# 15_BoardPowerSupply.net
KiCad netlist of a schematic drawn in Altium Designer
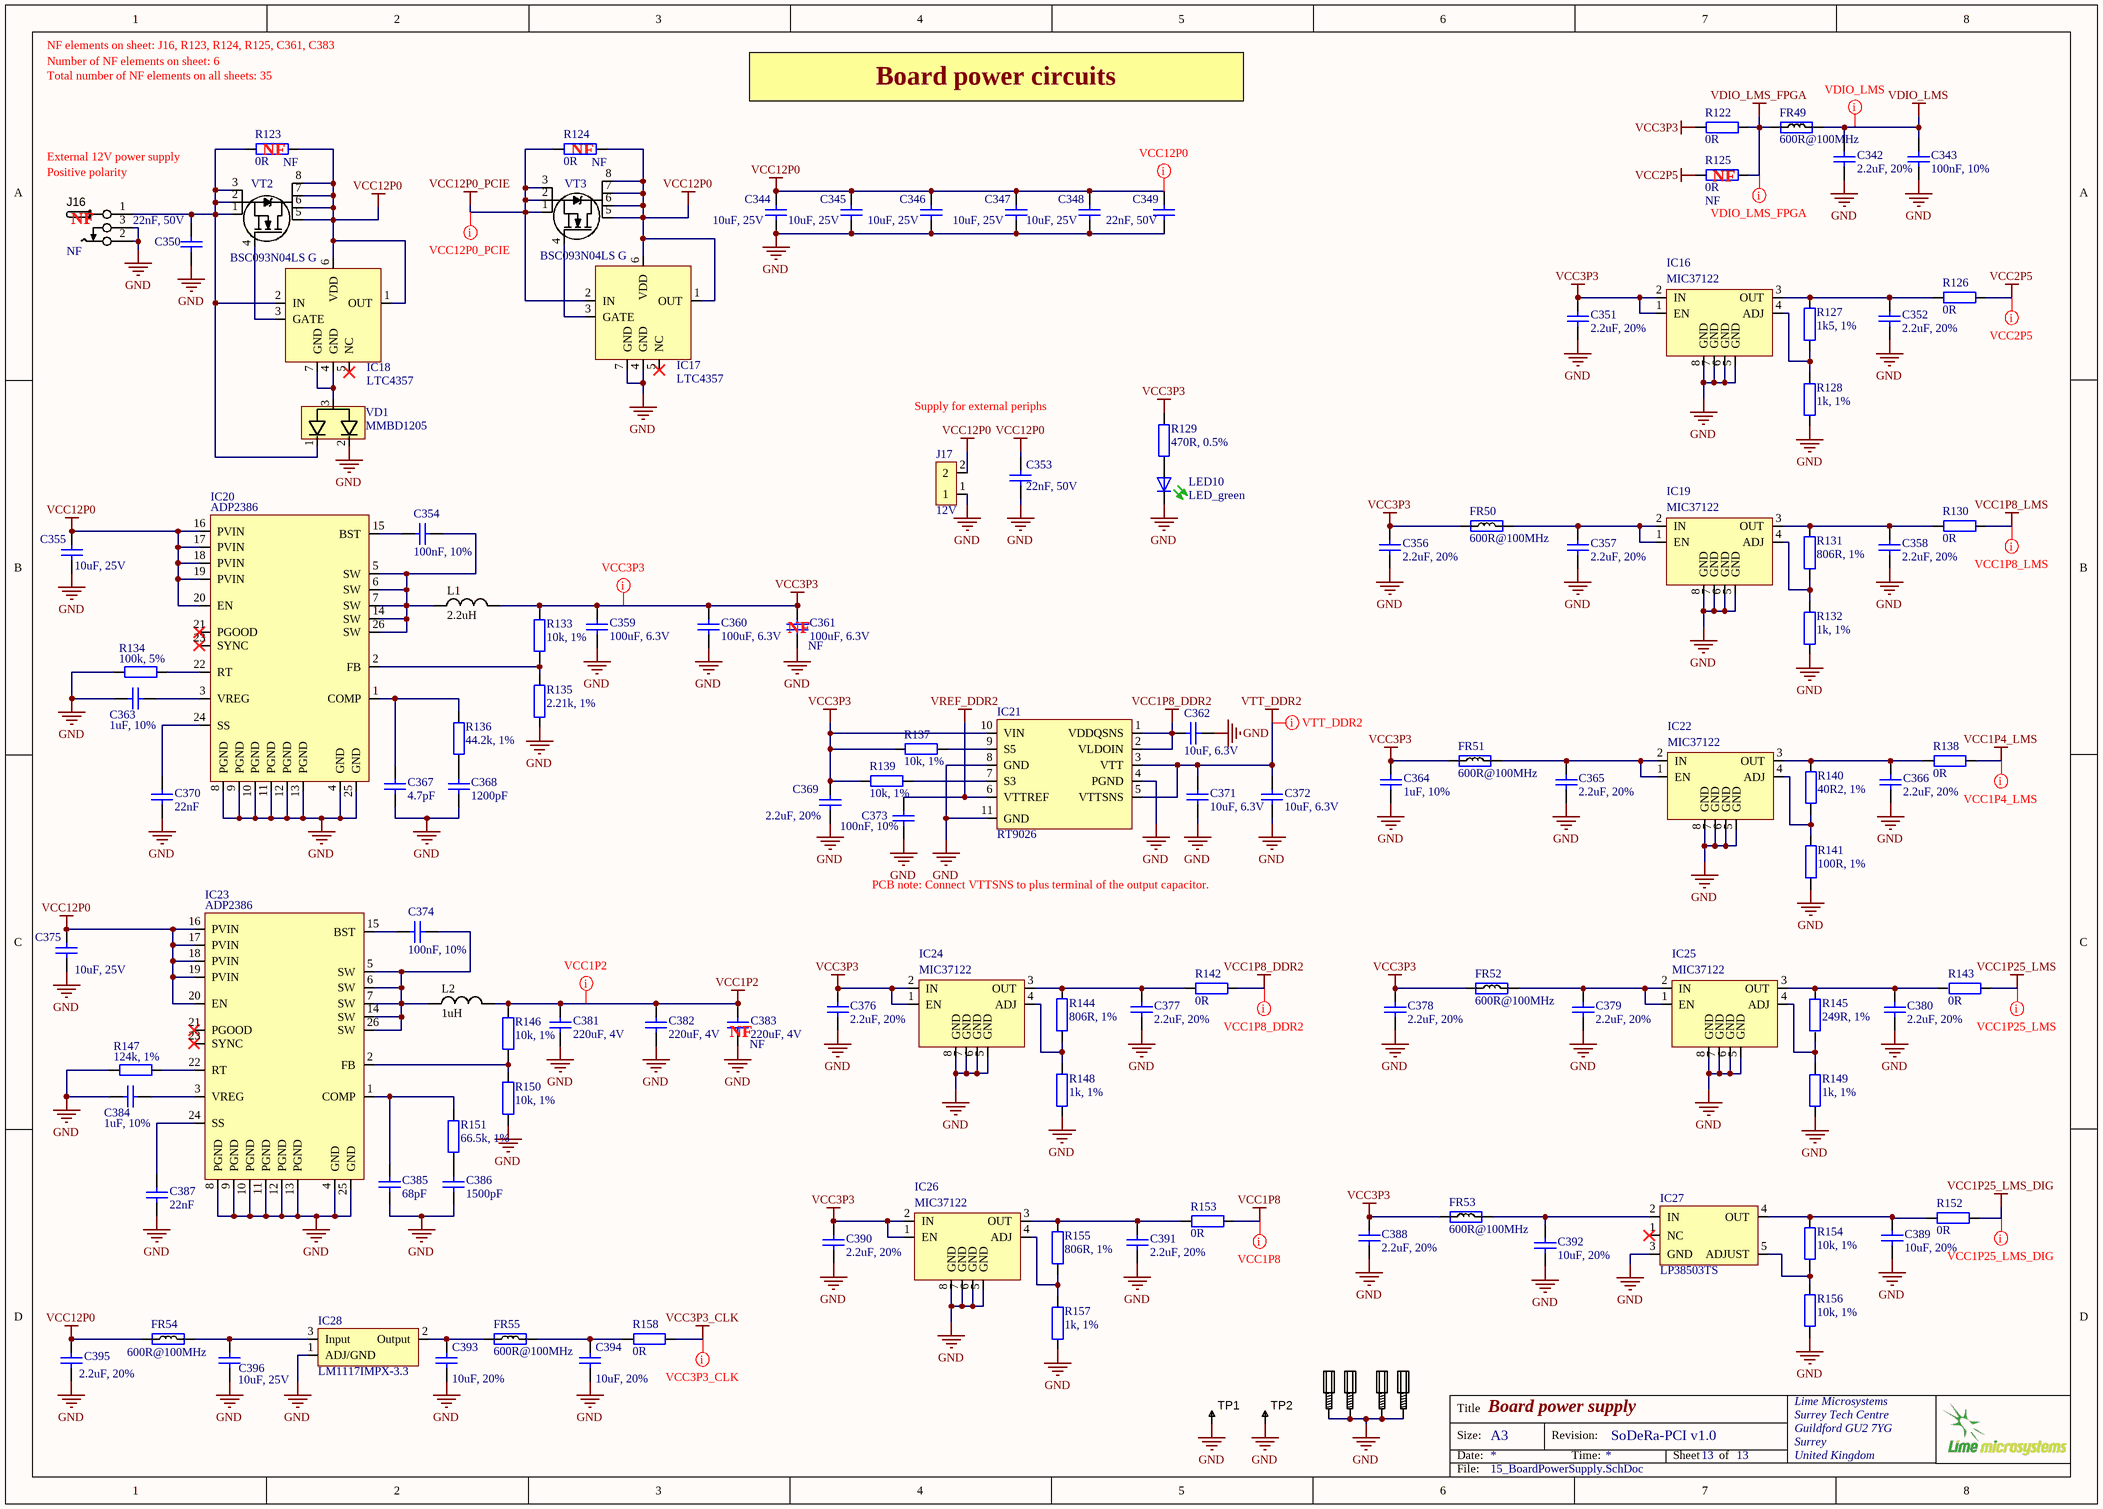
[diagram p0: 15_BoardPowerSupply.SchDoc]

(export (version "E")
  (design (tool "Eeschema 10.0.6"))
  (components
    (comp (ref "C342")
      (value "2.2uF, 20%")
      (footprint "LimeMicroAltiumLib_pcbLib:CAP0402")
      (fields (field (name "MANUFACTURER") "TDK Corporation") (field (name "TOLERANCE") "±20%"))
      (libsource (lib "LimeMicroAltiumLib_schLib") (part "Cap_0402"))
    )
    (comp (ref "C343")
      (value "100nF, 10%")
      (footprint "LimeMicroAltiumLib_pcbLib:CAP0402")
      (fields
        (field (name "MANUFACTURER") "Murata Electronics")
        (field (name "TOLERANCE") "10 %")
        (field (name "MANUFACTURER PART NUMBER") "GRM155R71C104KA88D")
      )
      (libsource (lib "LimeMicroAltiumLib_schLib") (part "Cap_0402"))
    )
    (comp (ref "C344")
      (value "10uF, 25V")
      (footprint "LimeMicroAltiumLib_pcbLib:CAP0603")
      (fields
        (field (name "MANUFACTURER") "Murata Electronics North America")
        (field (name "MANUFACTURER PART NUMBER") "GRM188R61E106MA73D")
        (field (name "TOLERANCE") "±20%")
      )
      (libsource (lib "LimeMicroAltiumLib_schLib") (part "Cap_0603"))
    )
    (comp (ref "C345")
      (value "10uF, 25V")
      (footprint "LimeMicroAltiumLib_pcbLib:CAP0603")
      (fields
        (field (name "MANUFACTURER") "Murata Electronics North America")
        (field (name "MANUFACTURER PART NUMBER") "GRM188R61E106MA73D")
        (field (name "TOLERANCE") "±20%")
      )
      (libsource (lib "LimeMicroAltiumLib_schLib") (part "Cap_0603"))
    )
    (comp (ref "C346")
      (value "10uF, 25V")
      (footprint "LimeMicroAltiumLib_pcbLib:CAP0603")
      (fields
        (field (name "MANUFACTURER") "Murata Electronics North America")
        (field (name "MANUFACTURER PART NUMBER") "GRM188R61E106MA73D")
        (field (name "TOLERANCE") "±20%")
      )
      (libsource (lib "LimeMicroAltiumLib_schLib") (part "Cap_0603"))
    )
    (comp (ref "C347")
      (value "10uF, 25V")
      (footprint "LimeMicroAltiumLib_pcbLib:CAP0603")
      (fields
        (field (name "MANUFACTURER") "Murata Electronics North America")
        (field (name "MANUFACTURER PART NUMBER") "GRM188R61E106MA73D")
        (field (name "TOLERANCE") "±20%")
      )
      (libsource (lib "LimeMicroAltiumLib_schLib") (part "Cap_0603"))
    )
    (comp (ref "C348")
      (value "10uF, 25V")
      (footprint "LimeMicroAltiumLib_pcbLib:CAP0603")
      (fields
        (field (name "MANUFACTURER") "Murata Electronics North America")
        (field (name "MANUFACTURER PART NUMBER") "GRM188R61E106MA73D")
        (field (name "TOLERANCE") "±20%")
      )
      (libsource (lib "LimeMicroAltiumLib_schLib") (part "Cap_0603"))
    )
    (comp (ref "C349")
      (value "22nF, 50V")
      (footprint "LimeMicroAltiumLib_pcbLib:CAP0402")
      (fields (field (name "TOLERANCE") "±10%") (field (name "MANUFACTURER") "Kemet"))
      (libsource (lib "LimeMicroAltiumLib_schLib") (part "Cap_0402"))
    )
    (comp (ref "C350")
      (value "22nF, 50V")
      (footprint "LimeMicroAltiumLib_pcbLib:CAP0402")
      (fields (field (name "TOLERANCE") "±10%") (field (name "MANUFACTURER") "Kemet"))
      (libsource (lib "LimeMicroAltiumLib_schLib") (part "Cap_0402"))
    )
    (comp (ref "C351")
      (value "2.2uF, 20%")
      (footprint "LimeMicroAltiumLib_pcbLib:CAP0402")
      (fields (field (name "MANUFACTURER") "TDK Corporation") (field (name "TOLERANCE") "±20%"))
      (libsource (lib "LimeMicroAltiumLib_schLib") (part "Cap_0402"))
    )
    (comp (ref "C352")
      (value "2.2uF, 20%")
      (footprint "LimeMicroAltiumLib_pcbLib:CAP0402")
      (fields (field (name "MANUFACTURER") "TDK Corporation") (field (name "TOLERANCE") "±20%"))
      (libsource (lib "LimeMicroAltiumLib_schLib") (part "Cap_0402"))
    )
    (comp (ref "C353")
      (value "22nF, 50V")
      (footprint "LimeMicroAltiumLib_pcbLib:CAP0402")
      (fields (field (name "TOLERANCE") "±10%") (field (name "MANUFACTURER") "Kemet"))
      (libsource (lib "LimeMicroAltiumLib_schLib") (part "Cap_0402"))
    )
    (comp (ref "C354")
      (value "100nF, 10%")
      (footprint "LimeMicroAltiumLib_pcbLib:CAP0402")
      (fields
        (field (name "MANUFACTURER") "Murata Electronics")
        (field (name "TOLERANCE") "10 %")
        (field (name "MANUFACTURER PART NUMBER") "GRM155R71C104KA88D")
      )
      (libsource (lib "LimeMicroAltiumLib_schLib") (part "Cap_0402"))
    )
    (comp (ref "C355")
      (value "10uF, 25V")
      (footprint "LimeMicroAltiumLib_pcbLib:CAP0603")
      (fields
        (field (name "MANUFACTURER") "Murata Electronics North America")
        (field (name "MANUFACTURER PART NUMBER") "GRM188R61E106MA73D")
        (field (name "TOLERANCE") "±20%")
      )
      (libsource (lib "LimeMicroAltiumLib_schLib") (part "Cap_0603"))
    )
    (comp (ref "C356")
      (value "2.2uF, 20%")
      (footprint "LimeMicroAltiumLib_pcbLib:CAP0402")
      (fields (field (name "MANUFACTURER") "TDK Corporation") (field (name "TOLERANCE") "±20%"))
      (libsource (lib "LimeMicroAltiumLib_schLib") (part "Cap_0402"))
    )
    (comp (ref "C357")
      (value "2.2uF, 20%")
      (footprint "LimeMicroAltiumLib_pcbLib:CAP0402")
      (fields (field (name "MANUFACTURER") "TDK Corporation") (field (name "TOLERANCE") "±20%"))
      (libsource (lib "LimeMicroAltiumLib_schLib") (part "Cap_0402"))
    )
    (comp (ref "C358")
      (value "2.2uF, 20%")
      (footprint "LimeMicroAltiumLib_pcbLib:CAP0402")
      (fields (field (name "MANUFACTURER") "TDK Corporation") (field (name "TOLERANCE") "±20%"))
      (libsource (lib "LimeMicroAltiumLib_schLib") (part "Cap_0402"))
    )
    (comp (ref "C359")
      (value "100uF, 6.3V")
      (footprint "LimeMicroAltiumLib_pcbLib:CAP1206")
      (fields (field (name "MANUFACTURER") "MURATA"))
      (libsource (lib "LimeFPGAboard_schLib") (part "Cap_1206"))
    )
    (comp (ref "C360")
      (value "100uF, 6.3V")
      (footprint "LimeMicroAltiumLib_pcbLib:CAP1206")
      (fields (field (name "MANUFACTURER") "MURATA"))
      (libsource (lib "LimeFPGAboard_schLib") (part "Cap_1206"))
    )
    (comp (ref "C361")
      (value "100uF, 6.3V")
      (footprint "LimeMicroAltiumLib_pcbLib:CAP1206")
      (fields (field (name "MANUFACTURER") "MURATA") (field (name "ASSEMBLY INFO") "NF"))
      (libsource (lib "LimeFPGAboard_schLib") (part "Cap_1206"))
    )
    (comp (ref "C362")
      (value "10uF, 6.3V")
      (footprint "LimeMicroAltiumLib_pcbLib:CAP0603")
      (fields (field (name "TOLERANCE") "±20%"))
      (libsource (lib "LimeFPGAboard_schLib") (part "Cap_0603"))
    )
    (comp (ref "C363")
      (value "1uF, 10%")
      (footprint "LimeMicroAltiumLib_pcbLib:CAP0402")
      (fields (field (name "MANUFACTURER") "TDK"))
      (libsource (lib "LimeMicroAltiumLib_schLib") (part "Cap_0402"))
    )
    (comp (ref "C364")
      (value "1uF, 10%")
      (footprint "LimeMicroAltiumLib_pcbLib:CAP0402")
      (fields (field (name "MANUFACTURER") "TDK"))
      (libsource (lib "LimeMicroAltiumLib_schLib") (part "Cap_0402"))
    )
    (comp (ref "C365")
      (value "2.2uF, 20%")
      (footprint "LimeMicroAltiumLib_pcbLib:CAP0402")
      (fields (field (name "MANUFACTURER") "TDK Corporation") (field (name "TOLERANCE") "±20%"))
      (libsource (lib "LimeMicroAltiumLib_schLib") (part "Cap_0402"))
    )
    (comp (ref "C366")
      (value "2.2uF, 20%")
      (footprint "LimeMicroAltiumLib_pcbLib:CAP0402")
      (fields (field (name "MANUFACTURER") "TDK Corporation") (field (name "TOLERANCE") "±20%"))
      (libsource (lib "LimeMicroAltiumLib_schLib") (part "Cap_0402"))
    )
    (comp (ref "C367")
      (value "4.7pF")
      (footprint "LimeMicroAltiumLib_pcbLib:CAP0402")
      (fields (field (name "MANUFACTURER") "MURATA"))
      (libsource (lib "LimeMicroAltiumLib_schLib") (part "Cap_0402"))
    )
    (comp (ref "C368")
      (value "1200pF")
      (footprint "LimeMicroAltiumLib_pcbLib:CAP0402")
      (fields (field (name "MANUFACTURER") "Kemet") (field (name "TOLERANCE") "±5%"))
      (libsource (lib "LimeMicroAltiumLib_schLib") (part "Cap_0402"))
    )
    (comp (ref "C369")
      (value "2.2uF, 20%")
      (footprint "LimeMicroAltiumLib_pcbLib:CAP0402")
      (fields (field (name "MANUFACTURER") "TDK Corporation") (field (name "TOLERANCE") "±20%"))
      (libsource (lib "LimeMicroAltiumLib_schLib") (part "Cap_0402"))
    )
    (comp (ref "C370")
      (value "22nF")
      (footprint "LimeMicroAltiumLib_pcbLib:CAP0402")
      (fields (field (name "TOLERANCE") "±10%") (field (name "MANUFACTURER") "Kemet"))
      (libsource (lib "LimeMicroAltiumLib_schLib") (part "Cap_0402"))
    )
    (comp (ref "C371")
      (value "10uF, 6.3V")
      (footprint "LimeMicroAltiumLib_pcbLib:CAP0603")
      (fields (field (name "TOLERANCE") "±20%"))
      (libsource (lib "LimeFPGAboard_schLib") (part "Cap_0603"))
    )
    (comp (ref "C372")
      (value "10uF, 6.3V")
      (footprint "LimeMicroAltiumLib_pcbLib:CAP0603")
      (fields (field (name "TOLERANCE") "±20%"))
      (libsource (lib "LimeFPGAboard_schLib") (part "Cap_0603"))
    )
    (comp (ref "C373")
      (value "100nF, 10%")
      (footprint "LimeMicroAltiumLib_pcbLib:CAP0402")
      (fields
        (field (name "MANUFACTURER") "Murata Electronics")
        (field (name "TOLERANCE") "10 %")
        (field (name "MANUFACTURER PART NUMBER") "GRM155R71C104KA88D")
      )
      (libsource (lib "LimeMicroAltiumLib_schLib") (part "Cap_0402"))
    )
    (comp (ref "C374")
      (value "100nF, 10%")
      (footprint "LimeMicroAltiumLib_pcbLib:CAP0402")
      (fields
        (field (name "MANUFACTURER") "Murata Electronics")
        (field (name "TOLERANCE") "10 %")
        (field (name "MANUFACTURER PART NUMBER") "GRM155R71C104KA88D")
      )
      (libsource (lib "LimeMicroAltiumLib_schLib") (part "Cap_0402"))
    )
    (comp (ref "C375")
      (value "10uF, 25V")
      (footprint "LimeMicroAltiumLib_pcbLib:CAP0603")
      (fields
        (field (name "MANUFACTURER") "Murata Electronics North America")
        (field (name "MANUFACTURER PART NUMBER") "GRM188R61E106MA73D")
        (field (name "TOLERANCE") "±20%")
      )
      (libsource (lib "LimeMicroAltiumLib_schLib") (part "Cap_0603"))
    )
    (comp (ref "C376")
      (value "2.2uF, 20%")
      (footprint "LimeMicroAltiumLib_pcbLib:CAP0402")
      (fields (field (name "MANUFACTURER") "TDK Corporation") (field (name "TOLERANCE") "±20%"))
      (libsource (lib "LimeMicroAltiumLib_schLib") (part "Cap_0402"))
    )
    (comp (ref "C377")
      (value "2.2uF, 20%")
      (footprint "LimeMicroAltiumLib_pcbLib:CAP0402")
      (fields (field (name "MANUFACTURER") "TDK Corporation") (field (name "TOLERANCE") "±20%"))
      (libsource (lib "LimeMicroAltiumLib_schLib") (part "Cap_0402"))
    )
    (comp (ref "C378")
      (value "2.2uF, 20%")
      (footprint "LimeMicroAltiumLib_pcbLib:CAP0402")
      (fields (field (name "MANUFACTURER") "TDK Corporation") (field (name "TOLERANCE") "±20%"))
      (libsource (lib "LimeMicroAltiumLib_schLib") (part "Cap_0402"))
    )
    (comp (ref "C379")
      (value "2.2uF, 20%")
      (footprint "LimeMicroAltiumLib_pcbLib:CAP0402")
      (fields (field (name "MANUFACTURER") "TDK Corporation") (field (name "TOLERANCE") "±20%"))
      (libsource (lib "LimeMicroAltiumLib_schLib") (part "Cap_0402"))
    )
    (comp (ref "C380")
      (value "2.2uF, 20%")
      (footprint "LimeMicroAltiumLib_pcbLib:CAP0402")
      (fields (field (name "MANUFACTURER") "TDK Corporation") (field (name "TOLERANCE") "±20%"))
      (libsource (lib "LimeMicroAltiumLib_schLib") (part "Cap_0402"))
    )
    (comp (ref "C381")
      (value "220uF, 4V")
      (footprint "LimeMicroAltiumLib_pcbLib:CAP1206")
      (fields
        (field (name "MANUFACTURER PART NUMBER") "GRM31CR60G227ME11L")
        (field (name "MANUFACTURER") "Murata Electronics North America")
        (field (name "TOLERANCE") "±20%")
      )
      (libsource (lib "LimeFPGAboard_schLib") (part "Cap_1206"))
    )
    (comp (ref "C382")
      (value "220uF, 4V")
      (footprint "LimeMicroAltiumLib_pcbLib:CAP1206")
      (fields
        (field (name "MANUFACTURER PART NUMBER") "GRM31CR60G227ME11L")
        (field (name "MANUFACTURER") "Murata Electronics North America")
        (field (name "TOLERANCE") "±20%")
      )
      (libsource (lib "LimeFPGAboard_schLib") (part "Cap_1206"))
    )
    (comp (ref "C383")
      (value "220uF, 4V")
      (footprint "LimeMicroAltiumLib_pcbLib:CAP1206")
      (fields
        (field (name "MANUFACTURER PART NUMBER") "GRM31CR60G227ME11L")
        (field (name "MANUFACTURER") "Murata Electronics North America")
        (field (name "TOLERANCE") "±20%")
        (field (name "ASSEMBLY INFO") "NF")
      )
      (libsource (lib "LimeFPGAboard_schLib") (part "Cap_1206"))
    )
    (comp (ref "C384")
      (value "1uF, 10%")
      (footprint "LimeMicroAltiumLib_pcbLib:CAP0402")
      (fields (field (name "MANUFACTURER") "TDK"))
      (libsource (lib "LimeMicroAltiumLib_schLib") (part "Cap_0402"))
    )
    (comp (ref "C385")
      (value "68pF")
      (footprint "LimeMicroAltiumLib_pcbLib:CAP0402")
      (fields (field (name "TOLERANCE") "±1%") (field (name "MANUFACTURER") "Kemet"))
      (libsource (lib "LimeMicroAltiumLib_schLib") (part "Cap_0402"))
    )
    (comp (ref "C386")
      (value "1500pF")
      (footprint "LimeMicroAltiumLib_pcbLib:CAP0402")
      (fields
        (field (name "MANUFACTURER") "Samsung Electro-Mechanics America, Inc.")
        (field (name "TOLERANCE") "±10%")
      )
      (libsource (lib "LimeMicroAltiumLib_schLib") (part "Cap_0402"))
    )
    (comp (ref "C387")
      (value "22nF")
      (footprint "LimeMicroAltiumLib_pcbLib:CAP0402")
      (fields (field (name "TOLERANCE") "±10%") (field (name "MANUFACTURER") "Kemet"))
      (libsource (lib "LimeMicroAltiumLib_schLib") (part "Cap_0402"))
    )
    (comp (ref "C388")
      (value "2.2uF, 20%")
      (footprint "LimeMicroAltiumLib_pcbLib:CAP0402")
      (fields (field (name "MANUFACTURER") "TDK Corporation") (field (name "TOLERANCE") "±20%"))
      (libsource (lib "LimeMicroAltiumLib_schLib") (part "Cap_0402"))
    )
    (comp (ref "C389")
      (value "10uF, 20%")
      (footprint "LimeMicroAltiumLib_pcbLib:CAP0603")
      (fields (field (name "MANUFACTURER") "Yageo") (field (name "TOLERANCE") "±20%"))
      (libsource (lib "LimeMicroAltiumLib_schLib") (part "Cap_0603"))
    )
    (comp (ref "C390")
      (value "2.2uF, 20%")
      (footprint "LimeMicroAltiumLib_pcbLib:CAP0402")
      (fields (field (name "MANUFACTURER") "TDK Corporation") (field (name "TOLERANCE") "±20%"))
      (libsource (lib "LimeMicroAltiumLib_schLib") (part "Cap_0402"))
    )
    (comp (ref "C391")
      (value "2.2uF, 20%")
      (footprint "LimeMicroAltiumLib_pcbLib:CAP0402")
      (fields (field (name "MANUFACTURER") "TDK Corporation") (field (name "TOLERANCE") "±20%"))
      (libsource (lib "LimeMicroAltiumLib_schLib") (part "Cap_0402"))
    )
    (comp (ref "C392")
      (value "10uF, 20%")
      (footprint "LimeMicroAltiumLib_pcbLib:CAP0603")
      (fields (field (name "MANUFACTURER") "Yageo") (field (name "TOLERANCE") "±20%"))
      (libsource (lib "LimeMicroAltiumLib_schLib") (part "Cap_0603"))
    )
    (comp (ref "C393")
      (value "10uF, 20%")
      (footprint "LimeMicroAltiumLib_pcbLib:CAP0603")
      (fields (field (name "MANUFACTURER") "Yageo") (field (name "TOLERANCE") "±20%"))
      (libsource (lib "LimeMicroAltiumLib_schLib") (part "Cap_0603"))
    )
    (comp (ref "C394")
      (value "10uF, 20%")
      (footprint "LimeMicroAltiumLib_pcbLib:CAP0603")
      (fields (field (name "MANUFACTURER") "Yageo") (field (name "TOLERANCE") "±20%"))
      (libsource (lib "LimeMicroAltiumLib_schLib") (part "Cap_0603"))
    )
    (comp (ref "C395")
      (value "2.2uF, 20%")
      (footprint "LimeMicroAltiumLib_pcbLib:CAP0402")
      (fields (field (name "MANUFACTURER") "TDK Corporation") (field (name "TOLERANCE") "±20%"))
      (libsource (lib "LimeMicroAltiumLib_schLib") (part "Cap_0402"))
    )
    (comp (ref "C396")
      (value "10uF, 25V")
      (footprint "LimeMicroAltiumLib_pcbLib:CAP0603")
      (fields
        (field (name "MANUFACTURER") "Murata Electronics North America")
        (field (name "MANUFACTURER PART NUMBER") "GRM188R61E106MA73D")
        (field (name "TOLERANCE") "±20%")
      )
      (libsource (lib "LimeMicroAltiumLib_schLib") (part "Cap_0603"))
    )
    (comp (ref "FR49")
      (value "600R@100MHz")
      (footprint "LimeMicroAltiumLib_pcbLib:RES0805")
      (fields (field (name "MANUFACTURER") "TDK Corporation"))
      (libsource (lib "LimeMicroAltiumLib_schLib") (part "Ferrite"))
    )
    (comp (ref "FR50")
      (value "600R@100MHz")
      (footprint "LimeMicroAltiumLib_pcbLib:RES0805")
      (fields (field (name "MANUFACTURER") "TDK Corporation"))
      (libsource (lib "LimeMicroAltiumLib_schLib") (part "Ferrite"))
    )
    (comp (ref "FR51")
      (value "600R@100MHz")
      (footprint "LimeMicroAltiumLib_pcbLib:RES0805")
      (fields (field (name "MANUFACTURER") "TDK Corporation"))
      (libsource (lib "LimeMicroAltiumLib_schLib") (part "Ferrite"))
    )
    (comp (ref "FR52")
      (value "600R@100MHz")
      (footprint "LimeMicroAltiumLib_pcbLib:RES0805")
      (fields (field (name "MANUFACTURER") "TDK Corporation"))
      (libsource (lib "LimeMicroAltiumLib_schLib") (part "Ferrite"))
    )
    (comp (ref "FR53")
      (value "600R@100MHz")
      (footprint "LimeMicroAltiumLib_pcbLib:RES0805")
      (fields (field (name "MANUFACTURER") "TDK Corporation"))
      (libsource (lib "LimeMicroAltiumLib_schLib") (part "Ferrite"))
    )
    (comp (ref "FR54")
      (value "600R@100MHz")
      (footprint "LimeMicroAltiumLib_pcbLib:RES0805")
      (fields (field (name "MANUFACTURER") "TDK Corporation"))
      (libsource (lib "LimeMicroAltiumLib_schLib") (part "Ferrite"))
    )
    (comp (ref "FR55")
      (value "600R@100MHz")
      (footprint "LimeMicroAltiumLib_pcbLib:RES0805")
      (fields (field (name "MANUFACTURER") "TDK Corporation"))
      (libsource (lib "LimeMicroAltiumLib_schLib") (part "Ferrite"))
    )
    (comp (ref "IC16")
      (value "MIC37122")
      (footprint "LimeMicroAltiumLib_pcbLib:MIC37122YM TR_SO8")
      (libsource (lib "LimeMicroAltiumLib_schLib") (part "MIC37122"))
    )
    (comp (ref "IC17")
      (value "LTC4357")
      (footprint "LimeMicroAltiumLib_pcbLib:LTC4357")
      (fields (field (name "MANUFACTURER PART NUMBER") "LTC4357IDCB#TRMPBF"))
      (libsource (lib "LimeFPGAboard_schLib") (part "LTC4357"))
    )
    (comp (ref "IC18")
      (value "LTC4357")
      (footprint "LimeMicroAltiumLib_pcbLib:LTC4357")
      (fields (field (name "MANUFACTURER PART NUMBER") "LTC4357IDCB#TRMPBF"))
      (libsource (lib "LimeFPGAboard_schLib") (part "LTC4357"))
    )
    (comp (ref "IC19")
      (value "MIC37122")
      (footprint "LimeMicroAltiumLib_pcbLib:MIC37122YM TR_SO8")
      (libsource (lib "LimeMicroAltiumLib_schLib") (part "MIC37122"))
    )
    (comp (ref "IC20")
      (value "ADP2386")
      (footprint "LimeMicroAltiumLib_pcbLib:ADP2386")
      (fields
        (field (name "MANUFACTURER PART NUMBER") "ADP2386ACPZN-R7")
        (field (name "MANUFACTURER") "Analog Devices Inc.")
      )
      (libsource (lib "LimeMicroAltiumLib_schLib") (part "ADP2386"))
    )
    (comp (ref "IC21")
      (value "RT9026")
      (footprint "LimeMicroAltiumLib_pcbLib:MSOP10")
      (fields (field (name "MANUFACTURER") "Richtek USA Inc."))
      (libsource (lib "LimeMicroAltiumLib_schLib") (part "RT9026"))
    )
    (comp (ref "IC22")
      (value "MIC37122")
      (footprint "LimeMicroAltiumLib_pcbLib:MIC37122YM TR_SO8")
      (libsource (lib "LimeMicroAltiumLib_schLib") (part "MIC37122"))
    )
    (comp (ref "IC23")
      (value "ADP2386")
      (footprint "LimeMicroAltiumLib_pcbLib:ADP2386")
      (fields (field (name "MANUFACTURER") "Analog Devices Inc."))
      (libsource (lib "LimeMicroAltiumLib_schLib") (part "ADP2386"))
    )
    (comp (ref "IC24")
      (value "MIC37122")
      (footprint "LimeMicroAltiumLib_pcbLib:MIC37122YM TR_SO8")
      (libsource (lib "LimeMicroAltiumLib_schLib") (part "MIC37122"))
    )
    (comp (ref "IC25")
      (value "MIC37122")
      (footprint "LimeMicroAltiumLib_pcbLib:MIC37122YM TR_SO8")
      (libsource (lib "LimeMicroAltiumLib_schLib") (part "MIC37122"))
    )
    (comp (ref "IC26")
      (value "MIC37122")
      (footprint "LimeMicroAltiumLib_pcbLib:MIC37122YM TR_SO8")
      (libsource (lib "LimeMicroAltiumLib_schLib") (part "MIC37122"))
    )
    (comp (ref "IC27")
      (value "LP38503TS")
      (footprint "LimeMicroAltiumLib_pcbLib:TO-263-5_v2")
      (fields
        (field (name "MANUFACTURER PART NUMBER") "LP38503TS-ADJ/NOPB")
        (field (name "MANUFACTURER") "Texas Instruments")
      )
      (libsource (lib "LimeMicroAltiumLib_schLib") (part "LP38503TS"))
    )
    (comp (ref "IC28")
      (value "LM1117IMPX-3.3")
      (footprint "LimeMicroAltiumLib_pcbLib:sot223")
      (fields (field (name "MANUFACTURER") "Texas Instruments"))
      (libsource (lib "LimeMicroAltiumLib_schLib") (part "LM1117IMPX-3.3"))
    )
    (comp (ref "J16")
      (value "CONN_PWR_JACK_2.1x5.5mm")
      (footprint "LimeMicroAltiumLib_pcbLib:CONN_PWR_JACK_v2")
      (description "Power Connector, THT, 2.1mm ID, 5.5mm OD")
      (fields (field (name "MANUFACTURER") "SWITCHCRAFT") (field (name "ASSEMBLY INFO") "NF"))
      (libsource (lib "LimeFPGAboard_schLib") (part "CONN_PWR_JACK_2.1x5.5mm"))
    )
    (comp (ref "J17")
      (value "12V")
      (footprint "LimeMicroAltiumLib_pcbLib:HDR_1x2")
      (libsource (lib "LimeFPGAboard_schLib") (part "Jumper"))
    )
    (comp (ref "L1")
      (value "2.2uH")
      (footprint "LimeMicroAltiumLib_pcbLib:FDVE1040_TOKO_INDUCTOR")
      (fields (field (name "TOLERANCE") "±20%") (field (name "MANUFACTURER") "Vishay Dale"))
      (libsource (lib "LimeMicroAltiumLib_schLib") (part "Inductor_0603"))
    )
    (comp (ref "L2")
      (value "1uH")
      (footprint "LimeMicroAltiumLib_pcbLib:FDVE1040_TOKO_INDUCTOR")
      (fields (field (name "TOLERANCE") "±20%") (field (name "MANUFACTURER") "Vishay Dale"))
      (libsource (lib "LimeMicroAltiumLib_schLib") (part "Inductor_0603"))
    )
    (comp (ref "LED10")
      (value "LED_green")
      (footprint "LimeMicroAltiumLib_pcbLib:LED-0603-GREEN")
      (libsource (lib "LimeFPGAboard_schLib") (part "LED_green"))
    )
    (comp (ref "MECH1")
      (value "# pcs.")
      (footprint "LimeMicroAltiumLib_pcbLib:PCB_standoff")
      (description "STANDOFF M/F MET 5MM HEX 10MM L")
      (libsource (lib "LimeMicroAltiumLib_schLib") (part "STANDOFF_M-F_THREADED_M3x8x10mm_HEX_5mm dia"))
    )
    (comp (ref "MECH2")
      (value "# pcs.")
      (footprint "LimeMicroAltiumLib_pcbLib:PCB_standoff")
      (description "STANDOFF M/F MET 5MM HEX 10MM L")
      (libsource (lib "LimeMicroAltiumLib_schLib") (part "STANDOFF_M-F_THREADED_M3x8x10mm_HEX_5mm dia"))
    )
    (comp (ref "MECH3")
      (value "# pcs.")
      (footprint "PCB_standoff")
      (description "STANDOFF M/F MET 5MM HEX 10MM L")
      (libsource (lib "LimeMicroAltiumLib_schLib") (part "STANDOFF_M-F_THREADED_M3x8x10mm_HEX_5mm dia"))
    )
    (comp (ref "MECH4")
      (value "# pcs.")
      (footprint "PCB_standoff")
      (description "STANDOFF M/F MET 5MM HEX 10MM L")
      (libsource (lib "LimeMicroAltiumLib_schLib") (part "STANDOFF_M-F_THREADED_M3x8x10mm_HEX_5mm dia"))
    )
    (comp (ref "R122")
      (value "0R")
      (footprint "LimeMicroAltiumLib_pcbLib:RES0402")
      (fields (field (name "MANUFACTURER") "Yageo") (field (name "TOLERANCE") "Jumper"))
      (libsource (lib "LimeMicroAltiumLib_schLib") (part "Res_0402"))
    )
    (comp (ref "R123")
      (value "0R")
      (footprint "LimeMicroAltiumLib_pcbLib:RES0805")
      (fields
        (field (name "ASSEMBLY INFO") "NF")
        (field (name "MANUFACTURER") "Vishay Dale")
        (field (name "TOLERANCE") "Jumper")
      )
      (libsource (lib "LimeMicroAltiumLib_schLib") (part "Res_0402"))
    )
    (comp (ref "R124")
      (value "0R")
      (footprint "LimeMicroAltiumLib_pcbLib:RES0805")
      (fields
        (field (name "ASSEMBLY INFO") "NF")
        (field (name "MANUFACTURER") "Vishay Dale")
        (field (name "TOLERANCE") "Jumper")
      )
      (libsource (lib "LimeMicroAltiumLib_schLib") (part "Res_0402"))
    )
    (comp (ref "R125")
      (value "0R")
      (footprint "LimeMicroAltiumLib_pcbLib:RES0402")
      (fields
        (field (name "ASSEMBLY INFO") "NF")
        (field (name "MANUFACTURER") "Yageo")
        (field (name "TOLERANCE") "Jumper")
      )
      (libsource (lib "LimeMicroAltiumLib_schLib") (part "Res_0402"))
    )
    (comp (ref "R126")
      (value "0R")
      (footprint "LimeMicroAltiumLib_pcbLib:RES0402")
      (fields (field (name "MANUFACTURER") "Yageo") (field (name "TOLERANCE") "Jumper"))
      (libsource (lib "LimeMicroAltiumLib_schLib") (part "Res_0402"))
    )
    (comp (ref "R127")
      (value "1k5, 1%")
      (footprint "LimeMicroAltiumLib_pcbLib:RES0402")
      (fields (field (name "MANUFACTURER") "Yageo") (field (name "TOLERANCE") "±1%"))
      (libsource (lib "LimeMicroAltiumLib_schLib") (part "Res_0402"))
    )
    (comp (ref "R128")
      (value "1k, 1%")
      (footprint "LimeMicroAltiumLib_pcbLib:RES0402")
      (fields (field (name "MANUFACTURER") "Stackpole Electronics Inc") (field (name "TOLERANCE") "±1%"))
      (libsource (lib "LimeMicroAltiumLib_schLib") (part "Res_0402"))
    )
    (comp (ref "R129")
      (value "470R, 0.5%")
      (footprint "LimeMicroAltiumLib_pcbLib:RES0402")
      (fields (field (name "TOLERANCE") "±0.5%"))
      (libsource (lib "LimeFPGAboard_schLib") (part "Res_0402"))
    )
    (comp (ref "R130")
      (value "0R")
      (footprint "LimeMicroAltiumLib_pcbLib:RES0402")
      (fields (field (name "MANUFACTURER") "Yageo") (field (name "TOLERANCE") "Jumper"))
      (libsource (lib "LimeMicroAltiumLib_schLib") (part "Res_0402"))
    )
    (comp (ref "R131")
      (value "806R, 1%")
      (footprint "LimeMicroAltiumLib_pcbLib:RES0402")
      (fields (field (name "TOLERANCE") "±1%") (field (name "MANUFACTURER") "Stackpole Electronics Inc"))
      (libsource (lib "LimeMicroAltiumLib_schLib") (part "Res_0402"))
    )
    (comp (ref "R132")
      (value "1k, 1%")
      (footprint "LimeMicroAltiumLib_pcbLib:RES0402")
      (fields (field (name "MANUFACTURER") "Stackpole Electronics Inc") (field (name "TOLERANCE") "±1%"))
      (libsource (lib "LimeMicroAltiumLib_schLib") (part "Res_0402"))
    )
    (comp (ref "R133")
      (value "10k, 1%")
      (footprint "LimeMicroAltiumLib_pcbLib:RES0402")
      (fields (field (name "MANUFACTURER") "Yageo") (field (name "TOLERANCE") "±1%"))
      (libsource (lib "LimeMicroAltiumLib_schLib") (part "Res_0402"))
    )
    (comp (ref "R134")
      (value "100k, 5%")
      (footprint "LimeMicroAltiumLib_pcbLib:RES0402")
      (fields
        (field (name "MANUFACTURER") "Panasonic Electronic Components")
        (field (name "MANUFACTURER PART NUMBER") "ERJ-2GEJ104X")
        (field (name "TOLERANCE") "±5%")
      )
      (libsource (lib "LimeMicroAltiumLib_schLib") (part "Res_0402"))
    )
    (comp (ref "R135")
      (value "2.21k, 1%")
      (footprint "LimeMicroAltiumLib_pcbLib:RES0402")
      (fields (field (name "MANUFACTURER") "Stackpole Electronics Inc.") (field (name "TOLERANCE") "±1%"))
      (libsource (lib "LimeMicroAltiumLib_schLib") (part "Res_0402"))
    )
    (comp (ref "R136")
      (value "44.2k, 1%")
      (footprint "LimeMicroAltiumLib_pcbLib:RES0402")
      (fields
        (field (name "TOLERANCE") "±1%")
        (field (name "MANUFACTURER") "Panasonic Electronic Components")
      )
      (libsource (lib "LimeMicroAltiumLib_schLib") (part "Res_0402"))
    )
    (comp (ref "R137")
      (value "10k, 1%")
      (footprint "LimeMicroAltiumLib_pcbLib:RES0402")
      (fields (field (name "MANUFACTURER") "Yageo") (field (name "TOLERANCE") "±1%"))
      (libsource (lib "LimeMicroAltiumLib_schLib") (part "Res_0402"))
    )
    (comp (ref "R138")
      (value "0R")
      (footprint "LimeMicroAltiumLib_pcbLib:RES0402")
      (fields (field (name "MANUFACTURER") "Yageo") (field (name "TOLERANCE") "Jumper"))
      (libsource (lib "LimeMicroAltiumLib_schLib") (part "Res_0402"))
    )
    (comp (ref "R139")
      (value "10k, 1%")
      (footprint "LimeMicroAltiumLib_pcbLib:RES0402")
      (fields (field (name "MANUFACTURER") "Yageo") (field (name "TOLERANCE") "±1%"))
      (libsource (lib "LimeMicroAltiumLib_schLib") (part "Res_0402"))
    )
    (comp (ref "R140")
      (value "40R2, 1%")
      (footprint "LimeMicroAltiumLib_pcbLib:RES0402")
      (fields (field (name "MANUFACTURER") "Stackpole Electronics Inc") (field (name "TOLERANCE") "±1%"))
      (libsource (lib "LimeMicroAltiumLib_schLib") (part "Res_0402"))
    )
    (comp (ref "R141")
      (value "100R, 1%")
      (footprint "LimeMicroAltiumLib_pcbLib:RES0402")
      (fields (field (name "TOLERANCE") "±1%") (field (name "MANUFACTURER") "Stackpole Electronics Inc"))
      (libsource (lib "LimeMicroAltiumLib_schLib") (part "Res_0402"))
    )
    (comp (ref "R142")
      (value "0R")
      (footprint "LimeMicroAltiumLib_pcbLib:RES0402")
      (fields (field (name "MANUFACTURER") "Yageo") (field (name "TOLERANCE") "Jumper"))
      (libsource (lib "LimeMicroAltiumLib_schLib") (part "Res_0402"))
    )
    (comp (ref "R143")
      (value "0R")
      (footprint "LimeMicroAltiumLib_pcbLib:RES0402")
      (fields (field (name "MANUFACTURER") "Yageo") (field (name "TOLERANCE") "Jumper"))
      (libsource (lib "LimeMicroAltiumLib_schLib") (part "Res_0402"))
    )
    (comp (ref "R144")
      (value "806R, 1%")
      (footprint "LimeMicroAltiumLib_pcbLib:RES0402")
      (fields (field (name "TOLERANCE") "±1%") (field (name "MANUFACTURER") "Stackpole Electronics Inc"))
      (libsource (lib "LimeMicroAltiumLib_schLib") (part "Res_0402"))
    )
    (comp (ref "R145")
      (value "249R, 1%")
      (footprint "LimeMicroAltiumLib_pcbLib:RES0402")
      (fields (field (name "MANUFACTURER") "Stackpole Electronics Inc") (field (name "TOLERANCE") "±1%"))
      (libsource (lib "LimeMicroAltiumLib_schLib") (part "Res_0402"))
    )
    (comp (ref "R146")
      (value "10k, 1%")
      (footprint "LimeMicroAltiumLib_pcbLib:RES0402")
      (fields (field (name "MANUFACTURER") "Yageo") (field (name "TOLERANCE") "±1%"))
      (libsource (lib "LimeMicroAltiumLib_schLib") (part "Res_0402"))
    )
    (comp (ref "R147")
      (value "124k, 1%")
      (footprint "LimeMicroAltiumLib_pcbLib:RES0402")
      (fields
        (field (name "MANUFACTURER") "Panasonic Electronic Components")
        (field (name "TOLERANCE") "±1%")
      )
      (libsource (lib "LimeMicroAltiumLib_schLib") (part "Res_0402"))
    )
    (comp (ref "R148")
      (value "1k, 1%")
      (footprint "LimeMicroAltiumLib_pcbLib:RES0402")
      (fields (field (name "MANUFACTURER") "Stackpole Electronics Inc") (field (name "TOLERANCE") "±1%"))
      (libsource (lib "LimeMicroAltiumLib_schLib") (part "Res_0402"))
    )
    (comp (ref "R149")
      (value "1k, 1%")
      (footprint "LimeMicroAltiumLib_pcbLib:RES0402")
      (fields (field (name "MANUFACTURER") "Stackpole Electronics Inc") (field (name "TOLERANCE") "±1%"))
      (libsource (lib "LimeMicroAltiumLib_schLib") (part "Res_0402"))
    )
    (comp (ref "R150")
      (value "10k, 1%")
      (footprint "LimeMicroAltiumLib_pcbLib:RES0402")
      (fields (field (name "MANUFACTURER") "Yageo") (field (name "TOLERANCE") "±1%"))
      (libsource (lib "LimeMicroAltiumLib_schLib") (part "Res_0402"))
    )
    (comp (ref "R151")
      (value "66.5k, 1%")
      (footprint "LimeMicroAltiumLib_pcbLib:RES0402")
      (fields
        (field (name "MANUFACTURER") "Panasonic Electronic Components")
        (field (name "TOLERANCE") "±1%")
      )
      (libsource (lib "LimeMicroAltiumLib_schLib") (part "Res_0402"))
    )
    (comp (ref "R152")
      (value "0R")
      (footprint "LimeMicroAltiumLib_pcbLib:RES0402")
      (fields (field (name "MANUFACTURER") "Yageo") (field (name "TOLERANCE") "Jumper"))
      (libsource (lib "LimeMicroAltiumLib_schLib") (part "Res_0402"))
    )
    (comp (ref "R153")
      (value "0R")
      (footprint "LimeMicroAltiumLib_pcbLib:RES0402")
      (fields (field (name "MANUFACTURER") "Yageo") (field (name "TOLERANCE") "Jumper"))
      (libsource (lib "LimeMicroAltiumLib_schLib") (part "Res_0402"))
    )
    (comp (ref "R154")
      (value "10k, 1%")
      (footprint "LimeMicroAltiumLib_pcbLib:RES0402")
      (fields (field (name "MANUFACTURER") "Yageo") (field (name "TOLERANCE") "±1%"))
      (libsource (lib "LimeMicroAltiumLib_schLib") (part "Res_0402"))
    )
    (comp (ref "R155")
      (value "806R, 1%")
      (footprint "LimeMicroAltiumLib_pcbLib:RES0402")
      (fields (field (name "TOLERANCE") "±1%") (field (name "MANUFACTURER") "Stackpole Electronics Inc"))
      (libsource (lib "LimeMicroAltiumLib_schLib") (part "Res_0402"))
    )
    (comp (ref "R156")
      (value "10k, 1%")
      (footprint "LimeMicroAltiumLib_pcbLib:RES0402")
      (fields (field (name "MANUFACTURER") "Yageo") (field (name "TOLERANCE") "±1%"))
      (libsource (lib "LimeMicroAltiumLib_schLib") (part "Res_0402"))
    )
    (comp (ref "R157")
      (value "1k, 1%")
      (footprint "LimeMicroAltiumLib_pcbLib:RES0402")
      (fields (field (name "MANUFACTURER") "Stackpole Electronics Inc") (field (name "TOLERANCE") "±1%"))
      (libsource (lib "LimeMicroAltiumLib_schLib") (part "Res_0402"))
    )
    (comp (ref "R158")
      (value "0R")
      (footprint "LimeMicroAltiumLib_pcbLib:RES0402")
      (fields (field (name "MANUFACTURER") "Yageo") (field (name "TOLERANCE") "Jumper"))
      (libsource (lib "LimeMicroAltiumLib_schLib") (part "Res_0402"))
    )
    (comp (ref "TP1")
      (value "TESTPOINT_THT_MINI")
      (footprint "TP-THT-MIDI")
      (description "Test Point PCB mount Miniature White")
      (fields (field (name "MANUFACTURER") "Keystone Electronics"))
      (libsource (lib "LimeMicroAltiumLib_schLib") (part "TESTPOINT_THT_MINI"))
    )
    (comp (ref "TP2")
      (value "TESTPOINT_THT_MINI")
      (footprint "TP-THT-MIDI")
      (description "Test Point PCB mount Miniature White")
      (fields (field (name "MANUFACTURER") "Keystone Electronics"))
      (libsource (lib "LimeMicroAltiumLib_schLib") (part "TESTPOINT_THT_MINI"))
    )
    (comp (ref "VD1")
      (value "MMBD1205")
      (footprint "LimeMicroAltiumLib_pcbLib:SOT23-3_v2")
      (libsource (lib "LimeFPGAboard_schLib") (part "MMBD1205"))
    )
    (comp (ref "VT2")
      (value "BSC093N04LS G")
      (footprint "LimeMicroAltiumLib_pcbLib:BSC093N04LS_G")
      (fields (field (name "MANUFACTURER") "Infineon Technologies"))
      (libsource (lib "LimeFPGAboard_schLib") (part "BSC093N04LS_G"))
    )
    (comp (ref "VT3")
      (value "BSC093N04LS G")
      (footprint "LimeMicroAltiumLib_pcbLib:BSC093N04LS_G")
      (fields (field (name "MANUFACTURER") "Infineon Technologies"))
      (libsource (lib "LimeFPGAboard_schLib") (part "BSC093N04LS_G"))
    )
  )
  (nets
    (net (code "1") (name "GND") (class "Default")
      (node (ref "C342") (pin "1") (pinfunction "1_1") (pintype "passive"))
      (node (ref "C343") (pin "2") (pinfunction "2_2") (pintype "passive"))
      (node (ref "C344") (pin "1") (pinfunction "1_1") (pintype "passive"))
      (node (ref "C345") (pin "1") (pinfunction "1_1") (pintype "passive"))
      (node (ref "C346") (pin "1") (pinfunction "1_1") (pintype "passive"))
      (node (ref "C347") (pin "1") (pinfunction "1_1") (pintype "passive"))
      (node (ref "C348") (pin "1") (pinfunction "1_1") (pintype "passive"))
      (node (ref "C349") (pin "2") (pinfunction "2_2") (pintype "passive"))
      (node (ref "C350") (pin "2") (pinfunction "2_2") (pintype "passive"))
      (node (ref "C351") (pin "1") (pinfunction "1_1") (pintype "passive"))
      (node (ref "C352") (pin "1") (pinfunction "1_1") (pintype "passive"))
      (node (ref "C353") (pin "2") (pinfunction "2_2") (pintype "passive"))
      (node (ref "C355") (pin "1") (pinfunction "1_1") (pintype "passive"))
      (node (ref "C356") (pin "1") (pinfunction "1_1") (pintype "passive"))
      (node (ref "C357") (pin "1") (pinfunction "1_1") (pintype "passive"))
      (node (ref "C358") (pin "1") (pinfunction "1_1") (pintype "passive"))
      (node (ref "C359") (pin "1") (pinfunction "1_1") (pintype "passive"))
      (node (ref "C360") (pin "1") (pinfunction "1_1") (pintype "passive"))
      (node (ref "C361") (pin "1") (pinfunction "1_1") (pintype "passive"))
      (node (ref "C362") (pin "1") (pinfunction "1_1") (pintype "passive"))
      (node (ref "C363") (pin "2") (pinfunction "2_2") (pintype "passive"))
      (node (ref "C364") (pin "1") (pinfunction "1_1") (pintype "passive"))
      (node (ref "C365") (pin "1") (pinfunction "1_1") (pintype "passive"))
      (node (ref "C366") (pin "1") (pinfunction "1_1") (pintype "passive"))
      (node (ref "C367") (pin "2") (pinfunction "2_2") (pintype "passive"))
      (node (ref "C368") (pin "2") (pinfunction "2_2") (pintype "passive"))
      (node (ref "C369") (pin "1") (pinfunction "1_1") (pintype "passive"))
      (node (ref "C370") (pin "2") (pinfunction "2_2") (pintype "passive"))
      (node (ref "C371") (pin "1") (pinfunction "1_1") (pintype "passive"))
      (node (ref "C372") (pin "1") (pinfunction "1_1") (pintype "passive"))
      (node (ref "C373") (pin "2") (pinfunction "2_2") (pintype "passive"))
      (node (ref "C375") (pin "1") (pinfunction "1_1") (pintype "passive"))
      (node (ref "C376") (pin "1") (pinfunction "1_1") (pintype "passive"))
      (node (ref "C377") (pin "1") (pinfunction "1_1") (pintype "passive"))
      (node (ref "C378") (pin "1") (pinfunction "1_1") (pintype "passive"))
      (node (ref "C379") (pin "1") (pinfunction "1_1") (pintype "passive"))
      (node (ref "C380") (pin "1") (pinfunction "1_1") (pintype "passive"))
      (node (ref "C381") (pin "1") (pinfunction "1_1") (pintype "passive"))
      (node (ref "C382") (pin "1") (pinfunction "1_1") (pintype "passive"))
      (node (ref "C383") (pin "1") (pinfunction "1_1") (pintype "passive"))
      (node (ref "C384") (pin "2") (pinfunction "2_2") (pintype "passive"))
      (node (ref "C385") (pin "2") (pinfunction "2_2") (pintype "passive"))
      (node (ref "C386") (pin "2") (pinfunction "2_2") (pintype "passive"))
      (node (ref "C387") (pin "2") (pinfunction "2_2") (pintype "passive"))
      (node (ref "C388") (pin "1") (pinfunction "1_1") (pintype "passive"))
      (node (ref "C389") (pin "1") (pinfunction "1_1") (pintype "passive"))
      (node (ref "C390") (pin "1") (pinfunction "1_1") (pintype "passive"))
      (node (ref "C391") (pin "1") (pinfunction "1_1") (pintype "passive"))
      (node (ref "C392") (pin "1") (pinfunction "1_1") (pintype "passive"))
      (node (ref "C393") (pin "1") (pinfunction "1_1") (pintype "passive"))
      (node (ref "C394") (pin "1") (pinfunction "1_1") (pintype "passive"))
      (node (ref "C395") (pin "1") (pinfunction "1_1") (pintype "passive"))
      (node (ref "C396") (pin "1") (pinfunction "1_1") (pintype "passive"))
      (node (ref "IC16") (pin "5") (pinfunction "GND_5") (pintype "passive"))
      (node (ref "IC16") (pin "6") (pinfunction "GND_6") (pintype "passive"))
      (node (ref "IC16") (pin "7") (pinfunction "GND_7") (pintype "passive"))
      (node (ref "IC16") (pin "8") (pinfunction "GND_8") (pintype "passive"))
      (node (ref "IC17") (pin "4") (pinfunction "GND_4") (pintype "passive"))
      (node (ref "IC17") (pin "7") (pinfunction "GND_7") (pintype "passive"))
      (node (ref "IC19") (pin "5") (pinfunction "GND_5") (pintype "passive"))
      (node (ref "IC19") (pin "6") (pinfunction "GND_6") (pintype "passive"))
      (node (ref "IC19") (pin "7") (pinfunction "GND_7") (pintype "passive"))
      (node (ref "IC19") (pin "8") (pinfunction "GND_8") (pintype "passive"))
      (node (ref "IC20") (pin "10") (pinfunction "PGND_10") (pintype "passive"))
      (node (ref "IC20") (pin "11") (pinfunction "PGND_11") (pintype "passive"))
      (node (ref "IC20") (pin "12") (pinfunction "PGND_12") (pintype "passive"))
      (node (ref "IC20") (pin "13") (pinfunction "PGND_13") (pintype "passive"))
      (node (ref "IC20") (pin "25") (pinfunction "GND_25") (pintype "passive"))
      (node (ref "IC20") (pin "4") (pinfunction "GND_4") (pintype "passive"))
      (node (ref "IC20") (pin "8") (pinfunction "PGND_8") (pintype "passive"))
      (node (ref "IC20") (pin "9") (pinfunction "PGND_9") (pintype "passive"))
      (node (ref "IC21") (pin "11") (pinfunction "GND_11") (pintype "passive"))
      (node (ref "IC21") (pin "4") (pinfunction "PGND_4") (pintype "passive"))
      (node (ref "IC21") (pin "8") (pinfunction "GND_8") (pintype "passive"))
      (node (ref "IC22") (pin "5") (pinfunction "GND_5") (pintype "passive"))
      (node (ref "IC22") (pin "6") (pinfunction "GND_6") (pintype "passive"))
      (node (ref "IC22") (pin "7") (pinfunction "GND_7") (pintype "passive"))
      (node (ref "IC22") (pin "8") (pinfunction "GND_8") (pintype "passive"))
      (node (ref "IC23") (pin "10") (pinfunction "PGND_10") (pintype "passive"))
      (node (ref "IC23") (pin "11") (pinfunction "PGND_11") (pintype "passive"))
      (node (ref "IC23") (pin "12") (pinfunction "PGND_12") (pintype "passive"))
      (node (ref "IC23") (pin "13") (pinfunction "PGND_13") (pintype "passive"))
      (node (ref "IC23") (pin "25") (pinfunction "GND_25") (pintype "passive"))
      (node (ref "IC23") (pin "4") (pinfunction "GND_4") (pintype "passive"))
      (node (ref "IC23") (pin "8") (pinfunction "PGND_8") (pintype "passive"))
      (node (ref "IC23") (pin "9") (pinfunction "PGND_9") (pintype "passive"))
      (node (ref "IC24") (pin "5") (pinfunction "GND_5") (pintype "passive"))
      (node (ref "IC24") (pin "6") (pinfunction "GND_6") (pintype "passive"))
      (node (ref "IC24") (pin "7") (pinfunction "GND_7") (pintype "passive"))
      (node (ref "IC24") (pin "8") (pinfunction "GND_8") (pintype "passive"))
      (node (ref "IC25") (pin "5") (pinfunction "GND_5") (pintype "passive"))
      (node (ref "IC25") (pin "6") (pinfunction "GND_6") (pintype "passive"))
      (node (ref "IC25") (pin "7") (pinfunction "GND_7") (pintype "passive"))
      (node (ref "IC25") (pin "8") (pinfunction "GND_8") (pintype "passive"))
      (node (ref "IC26") (pin "5") (pinfunction "GND_5") (pintype "passive"))
      (node (ref "IC26") (pin "6") (pinfunction "GND_6") (pintype "passive"))
      (node (ref "IC26") (pin "7") (pinfunction "GND_7") (pintype "passive"))
      (node (ref "IC26") (pin "8") (pinfunction "GND_8") (pintype "passive"))
      (node (ref "IC27") (pin "3") (pinfunction "GND_3") (pintype "passive"))
      (node (ref "IC28") (pin "1") (pinfunction "ADJ/GND_1") (pintype "passive"))
      (node (ref "J16") (pin "2") (pinfunction "2_2") (pintype "passive"))
      (node (ref "J16") (pin "3") (pinfunction "3_3") (pintype "passive"))
      (node (ref "J17") (pin "1") (pinfunction "1_1") (pintype "passive"))
      (node (ref "LED10") (pin "K") (pinfunction "C_K") (pintype "power_in"))
      (node (ref "MECH1") (pin "MH1") (pinfunction "MH1_MH1") (pintype "passive"))
      (node (ref "MECH2") (pin "MH1") (pinfunction "MH1_MH1") (pintype "passive"))
      (node (ref "MECH3") (pin "MH1") (pinfunction "MH1_MH1") (pintype "passive"))
      (node (ref "MECH4") (pin "MH1") (pinfunction "MH1_MH1") (pintype "passive"))
      (node (ref "R128") (pin "1") (pinfunction "1_1") (pintype "passive"))
      (node (ref "R132") (pin "1") (pinfunction "1_1") (pintype "passive"))
      (node (ref "R134") (pin "2") (pinfunction "2_2") (pintype "passive"))
      (node (ref "R135") (pin "1") (pinfunction "1_1") (pintype "passive"))
      (node (ref "R141") (pin "2") (pinfunction "2_2") (pintype "passive"))
      (node (ref "R147") (pin "2") (pinfunction "2_2") (pintype "passive"))
      (node (ref "R148") (pin "1") (pinfunction "1_1") (pintype "passive"))
      (node (ref "R149") (pin "1") (pinfunction "1_1") (pintype "passive"))
      (node (ref "R150") (pin "2") (pinfunction "2_2") (pintype "passive"))
      (node (ref "R156") (pin "2") (pinfunction "2_2") (pintype "passive"))
      (node (ref "R157") (pin "1") (pinfunction "1_1") (pintype "passive"))
      (node (ref "TP1") (pin "1") (pintype "passive"))
      (node (ref "TP2") (pin "1") (pintype "passive"))
      (node (ref "VD1") (pin "2") (pinfunction "2_2") (pintype "passive"))
    )
    (net (code "2") (name "Net-(C354-Pad2)") (class "Default")
      (node (ref "C354") (pin "2") (pinfunction "2_2") (pintype "passive"))
      (node (ref "IC20") (pin "14") (pinfunction "SW_14") (pintype "passive"))
      (node (ref "IC20") (pin "26") (pinfunction "SW_26") (pintype "passive"))
      (node (ref "IC20") (pin "5") (pinfunction "SW_5") (pintype "passive"))
      (node (ref "IC20") (pin "6") (pinfunction "SW_6") (pintype "passive"))
      (node (ref "IC20") (pin "7") (pinfunction "SW_7") (pintype "passive"))
      (node (ref "L1") (pin "1") (pinfunction "1_1") (pintype "passive"))
    )
    (net (code "3") (name "Net-(C368-Pad1)") (class "Default")
      (node (ref "C368") (pin "1") (pinfunction "1_1") (pintype "passive"))
      (node (ref "R136") (pin "1") (pinfunction "1_1") (pintype "passive"))
    )
    (net (code "4") (name "Net-(C374-Pad2)") (class "Default")
      (node (ref "C374") (pin "2") (pinfunction "2_2") (pintype "passive"))
      (node (ref "IC23") (pin "14") (pinfunction "SW_14") (pintype "passive"))
      (node (ref "IC23") (pin "26") (pinfunction "SW_26") (pintype "passive"))
      (node (ref "IC23") (pin "5") (pinfunction "SW_5") (pintype "passive"))
      (node (ref "IC23") (pin "6") (pinfunction "SW_6") (pintype "passive"))
      (node (ref "IC23") (pin "7") (pinfunction "SW_7") (pintype "passive"))
      (node (ref "L2") (pin "1") (pinfunction "1_1") (pintype "passive"))
    )
    (net (code "5") (name "Net-(C386-Pad1)") (class "Default")
      (node (ref "C386") (pin "1") (pinfunction "1_1") (pintype "passive"))
      (node (ref "R151") (pin "1") (pinfunction "1_1") (pintype "passive"))
    )
    (net (code "6") (name "Net-(C394-Pad2)") (class "Default")
      (node (ref "C394") (pin "2") (pinfunction "2_2") (pintype "passive"))
      (node (ref "FR55") (pin "2") (pinfunction "2_2") (pintype "passive"))
      (node (ref "R158") (pin "2") (pinfunction "2_2") (pintype "passive"))
    )
    (net (code "7") (name "Net-(IC16-ADJ)") (class "Default")
      (node (ref "IC16") (pin "4") (pinfunction "ADJ_4") (pintype "passive"))
      (node (ref "R127") (pin "2") (pinfunction "2_2") (pintype "passive"))
      (node (ref "R128") (pin "2") (pinfunction "2_2") (pintype "passive"))
    )
    (net (code "8") (name "Net-(IC16-OUT)") (class "Default")
      (node (ref "C352") (pin "2") (pinfunction "2_2") (pintype "passive"))
      (node (ref "IC16") (pin "3") (pinfunction "OUT_3") (pintype "passive"))
      (node (ref "R126") (pin "2") (pinfunction "2_2") (pintype "passive"))
      (node (ref "R127") (pin "1") (pinfunction "1_1") (pintype "passive"))
    )
    (net (code "9") (name "Net-(IC17-GATE)") (class "Default")
      (node (ref "IC17") (pin "3") (pinfunction "GATE_3") (pintype "passive"))
      (node (ref "VT3") (pin "4") (pinfunction "G_4") (pintype "passive"))
    )
    (net (code "10") (name "Net-(IC18-GATE)") (class "Default")
      (node (ref "IC18") (pin "3") (pinfunction "GATE_3") (pintype "passive"))
      (node (ref "VT2") (pin "4") (pinfunction "G_4") (pintype "passive"))
    )
    (net (code "11") (name "Net-(IC18-GND-Pad4)") (class "Default")
      (node (ref "IC18") (pin "4") (pinfunction "GND_4") (pintype "passive"))
      (node (ref "IC18") (pin "7") (pinfunction "GND_7") (pintype "passive"))
      (node (ref "VD1") (pin "3") (pinfunction "3_3") (pintype "passive"))
    )
    (net (code "12") (name "Net-(IC18-IN)") (class "Default")
      (node (ref "C350") (pin "1") (pinfunction "1_1") (pintype "passive"))
      (node (ref "IC18") (pin "2") (pinfunction "IN_2") (pintype "passive"))
      (node (ref "J16") (pin "1") (pinfunction "1_1") (pintype "passive"))
      (node (ref "R123") (pin "2") (pinfunction "2_2") (pintype "passive"))
      (node (ref "VD1") (pin "1") (pinfunction "1_1") (pintype "passive"))
      (node (ref "VT2") (pin "1") (pinfunction "S_1") (pintype "passive"))
      (node (ref "VT2") (pin "2") (pinfunction "S_2") (pintype "passive"))
      (node (ref "VT2") (pin "3") (pinfunction "S_3") (pintype "passive"))
    )
    (net (code "13") (name "Net-(IC19-ADJ)") (class "Default")
      (node (ref "IC19") (pin "4") (pinfunction "ADJ_4") (pintype "passive"))
      (node (ref "R131") (pin "2") (pinfunction "2_2") (pintype "passive"))
      (node (ref "R132") (pin "2") (pinfunction "2_2") (pintype "passive"))
    )
    (net (code "14") (name "Net-(IC19-EN)") (class "Default")
      (node (ref "C357") (pin "2") (pinfunction "2_2") (pintype "passive"))
      (node (ref "FR50") (pin "2") (pinfunction "2_2") (pintype "passive"))
      (node (ref "IC19") (pin "1") (pinfunction "EN_1") (pintype "passive"))
      (node (ref "IC19") (pin "2") (pinfunction "IN_2") (pintype "passive"))
    )
    (net (code "15") (name "Net-(IC19-OUT)") (class "Default")
      (node (ref "C358") (pin "2") (pinfunction "2_2") (pintype "passive"))
      (node (ref "IC19") (pin "3") (pinfunction "OUT_3") (pintype "passive"))
      (node (ref "R130") (pin "2") (pinfunction "2_2") (pintype "passive"))
      (node (ref "R131") (pin "1") (pinfunction "1_1") (pintype "passive"))
    )
    (net (code "16") (name "Net-(IC20-BST)") (class "Default")
      (node (ref "C354") (pin "1") (pinfunction "1_1") (pintype "passive"))
      (node (ref "IC20") (pin "15") (pinfunction "BST_15") (pintype "passive"))
    )
    (net (code "17") (name "Net-(IC20-COMP)") (class "Default")
      (node (ref "C367") (pin "1") (pinfunction "1_1") (pintype "passive"))
      (node (ref "IC20") (pin "1") (pinfunction "COMP_1") (pintype "passive"))
      (node (ref "R136") (pin "2") (pinfunction "2_2") (pintype "passive"))
    )
    (net (code "18") (name "Net-(IC20-FB)") (class "Default")
      (node (ref "IC20") (pin "2") (pinfunction "FB_2") (pintype "passive"))
      (node (ref "R133") (pin "2") (pinfunction "2_2") (pintype "passive"))
      (node (ref "R135") (pin "2") (pinfunction "2_2") (pintype "passive"))
    )
    (net (code "19") (name "Net-(IC20-RT)") (class "Default")
      (node (ref "IC20") (pin "22") (pinfunction "RT_22") (pintype "passive"))
      (node (ref "R134") (pin "1") (pinfunction "1_1") (pintype "passive"))
    )
    (net (code "20") (name "Net-(IC20-SS)") (class "Default")
      (node (ref "C370") (pin "1") (pinfunction "1_1") (pintype "passive"))
      (node (ref "IC20") (pin "24") (pinfunction "SS_24") (pintype "passive"))
    )
    (net (code "21") (name "Net-(IC20-VREG)") (class "Default")
      (node (ref "C363") (pin "1") (pinfunction "1_1") (pintype "passive"))
      (node (ref "IC20") (pin "3") (pinfunction "VREG_3") (pintype "passive"))
    )
    (net (code "22") (name "Net-(IC21-S3)") (class "Default")
      (node (ref "IC21") (pin "7") (pinfunction "S3_7") (pintype "passive"))
      (node (ref "R139") (pin "2") (pinfunction "2_2") (pintype "passive"))
    )
    (net (code "23") (name "Net-(IC21-S5)") (class "Default")
      (node (ref "IC21") (pin "9") (pinfunction "S5_9") (pintype "passive"))
      (node (ref "R137") (pin "2") (pinfunction "2_2") (pintype "passive"))
    )
    (net (code "24") (name "Net-(IC22-ADJ)") (class "Default")
      (node (ref "IC22") (pin "4") (pinfunction "ADJ_4") (pintype "passive"))
      (node (ref "R140") (pin "2") (pinfunction "2_2") (pintype "passive"))
      (node (ref "R141") (pin "1") (pinfunction "1_1") (pintype "passive"))
    )
    (net (code "25") (name "Net-(IC22-EN)") (class "Default")
      (node (ref "C365") (pin "2") (pinfunction "2_2") (pintype "passive"))
      (node (ref "FR51") (pin "2") (pinfunction "2_2") (pintype "passive"))
      (node (ref "IC22") (pin "1") (pinfunction "EN_1") (pintype "passive"))
      (node (ref "IC22") (pin "2") (pinfunction "IN_2") (pintype "passive"))
    )
    (net (code "26") (name "Net-(IC22-OUT)") (class "Default")
      (node (ref "C366") (pin "2") (pinfunction "2_2") (pintype "passive"))
      (node (ref "IC22") (pin "3") (pinfunction "OUT_3") (pintype "passive"))
      (node (ref "R138") (pin "2") (pinfunction "2_2") (pintype "passive"))
      (node (ref "R140") (pin "1") (pinfunction "1_1") (pintype "passive"))
    )
    (net (code "27") (name "Net-(IC23-BST)") (class "Default")
      (node (ref "C374") (pin "1") (pinfunction "1_1") (pintype "passive"))
      (node (ref "IC23") (pin "15") (pinfunction "BST_15") (pintype "passive"))
    )
    (net (code "28") (name "Net-(IC23-COMP)") (class "Default")
      (node (ref "C385") (pin "1") (pinfunction "1_1") (pintype "passive"))
      (node (ref "IC23") (pin "1") (pinfunction "COMP_1") (pintype "passive"))
      (node (ref "R151") (pin "2") (pinfunction "2_2") (pintype "passive"))
    )
    (net (code "29") (name "Net-(IC23-FB)") (class "Default")
      (node (ref "IC23") (pin "2") (pinfunction "FB_2") (pintype "passive"))
      (node (ref "R146") (pin "2") (pinfunction "2_2") (pintype "passive"))
      (node (ref "R150") (pin "1") (pinfunction "1_1") (pintype "passive"))
    )
    (net (code "30") (name "Net-(IC23-RT)") (class "Default")
      (node (ref "IC23") (pin "22") (pinfunction "RT_22") (pintype "passive"))
      (node (ref "R147") (pin "1") (pinfunction "1_1") (pintype "passive"))
    )
    (net (code "31") (name "Net-(IC23-SS)") (class "Default")
      (node (ref "C387") (pin "1") (pinfunction "1_1") (pintype "passive"))
      (node (ref "IC23") (pin "24") (pinfunction "SS_24") (pintype "passive"))
    )
    (net (code "32") (name "Net-(IC23-VREG)") (class "Default")
      (node (ref "C384") (pin "1") (pinfunction "1_1") (pintype "passive"))
      (node (ref "IC23") (pin "3") (pinfunction "VREG_3") (pintype "passive"))
    )
    (net (code "33") (name "Net-(IC24-ADJ)") (class "Default")
      (node (ref "IC24") (pin "4") (pinfunction "ADJ_4") (pintype "passive"))
      (node (ref "R144") (pin "2") (pinfunction "2_2") (pintype "passive"))
      (node (ref "R148") (pin "2") (pinfunction "2_2") (pintype "passive"))
    )
    (net (code "34") (name "Net-(IC24-OUT)") (class "Default")
      (node (ref "C377") (pin "2") (pinfunction "2_2") (pintype "passive"))
      (node (ref "IC24") (pin "3") (pinfunction "OUT_3") (pintype "passive"))
      (node (ref "R142") (pin "2") (pinfunction "2_2") (pintype "passive"))
      (node (ref "R144") (pin "1") (pinfunction "1_1") (pintype "passive"))
    )
    (net (code "35") (name "Net-(IC25-ADJ)") (class "Default")
      (node (ref "IC25") (pin "4") (pinfunction "ADJ_4") (pintype "passive"))
      (node (ref "R145") (pin "2") (pinfunction "2_2") (pintype "passive"))
      (node (ref "R149") (pin "2") (pinfunction "2_2") (pintype "passive"))
    )
    (net (code "36") (name "Net-(IC25-EN)") (class "Default")
      (node (ref "C379") (pin "2") (pinfunction "2_2") (pintype "passive"))
      (node (ref "FR52") (pin "2") (pinfunction "2_2") (pintype "passive"))
      (node (ref "IC25") (pin "1") (pinfunction "EN_1") (pintype "passive"))
      (node (ref "IC25") (pin "2") (pinfunction "IN_2") (pintype "passive"))
    )
    (net (code "37") (name "Net-(IC25-OUT)") (class "Default")
      (node (ref "C380") (pin "2") (pinfunction "2_2") (pintype "passive"))
      (node (ref "IC25") (pin "3") (pinfunction "OUT_3") (pintype "passive"))
      (node (ref "R143") (pin "2") (pinfunction "2_2") (pintype "passive"))
      (node (ref "R145") (pin "1") (pinfunction "1_1") (pintype "passive"))
    )
    (net (code "38") (name "Net-(IC26-ADJ)") (class "Default")
      (node (ref "IC26") (pin "4") (pinfunction "ADJ_4") (pintype "passive"))
      (node (ref "R155") (pin "2") (pinfunction "2_2") (pintype "passive"))
      (node (ref "R157") (pin "2") (pinfunction "2_2") (pintype "passive"))
    )
    (net (code "39") (name "Net-(IC26-OUT)") (class "Default")
      (node (ref "C391") (pin "2") (pinfunction "2_2") (pintype "passive"))
      (node (ref "IC26") (pin "3") (pinfunction "OUT_3") (pintype "passive"))
      (node (ref "R153") (pin "2") (pinfunction "2_2") (pintype "passive"))
      (node (ref "R155") (pin "1") (pinfunction "1_1") (pintype "passive"))
    )
    (net (code "40") (name "Net-(IC27-ADJUST)") (class "Default")
      (node (ref "IC27") (pin "5") (pinfunction "ADJUST_5") (pintype "passive"))
      (node (ref "R154") (pin "2") (pinfunction "2_2") (pintype "passive"))
      (node (ref "R156") (pin "1") (pinfunction "1_1") (pintype "passive"))
    )
    (net (code "41") (name "Net-(IC27-IN)") (class "Default")
      (node (ref "C392") (pin "2") (pinfunction "2_2") (pintype "passive"))
      (node (ref "FR53") (pin "2") (pinfunction "2_2") (pintype "passive"))
      (node (ref "IC27") (pin "2") (pinfunction "IN_2") (pintype "passive"))
    )
    (net (code "42") (name "Net-(IC27-OUT)") (class "Default")
      (node (ref "C389") (pin "2") (pinfunction "2_2") (pintype "passive"))
      (node (ref "IC27") (pin "4") (pinfunction "OUT_4") (pintype "passive"))
      (node (ref "R152") (pin "2") (pinfunction "2_2") (pintype "passive"))
      (node (ref "R154") (pin "1") (pinfunction "1_1") (pintype "passive"))
    )
    (net (code "43") (name "Net-(IC28-Input)") (class "Default")
      (node (ref "C396") (pin "2") (pinfunction "2_2") (pintype "passive"))
      (node (ref "FR54") (pin "2") (pinfunction "2_2") (pintype "passive"))
      (node (ref "IC28") (pin "3") (pinfunction "Input_3") (pintype "passive"))
    )
    (net (code "44") (name "Net-(IC28-Output)") (class "Default")
      (node (ref "C393") (pin "2") (pinfunction "2_2") (pintype "passive"))
      (node (ref "FR55") (pin "1") (pinfunction "1_1") (pintype "passive"))
      (node (ref "IC28") (pin "2") (pinfunction "Output_2") (pintype "passive"))
    )
    (net (code "45") (name "Net-(LED10-PadA)") (class "Default")
      (node (ref "LED10") (pin "A") (pinfunction "A_A") (pintype "power_in"))
      (node (ref "R129") (pin "1") (pinfunction "1_1") (pintype "passive"))
    )
    (net (code "46") (name "VCC1P2") (class "Default")
      (node (ref "C381") (pin "2") (pinfunction "2_2") (pintype "passive"))
      (node (ref "C382") (pin "2") (pinfunction "2_2") (pintype "passive"))
      (node (ref "C383") (pin "2") (pinfunction "2_2") (pintype "passive"))
      (node (ref "L2") (pin "2") (pinfunction "2_2") (pintype "passive"))
      (node (ref "R146") (pin "1") (pinfunction "1_1") (pintype "passive"))
    )
    (net (code "47") (name "VCC1P4_LMS") (class "Default")
      (node (ref "R138") (pin "1") (pinfunction "1_1") (pintype "passive"))
    )
    (net (code "48") (name "VCC1P8") (class "Default")
      (node (ref "R153") (pin "1") (pinfunction "1_1") (pintype "passive"))
    )
    (net (code "49") (name "VCC1P8_DDR2") (class "Default")
      (node (ref "C362") (pin "2") (pinfunction "2_2") (pintype "passive"))
      (node (ref "IC21") (pin "1") (pinfunction "VDDQSNS_1") (pintype "passive"))
      (node (ref "IC21") (pin "2") (pinfunction "VLDOIN_2") (pintype "passive"))
      (node (ref "R142") (pin "1") (pinfunction "1_1") (pintype "passive"))
    )
    (net (code "50") (name "VCC1P8_LMS") (class "Default")
      (node (ref "R130") (pin "1") (pinfunction "1_1") (pintype "passive"))
    )
    (net (code "51") (name "VCC1P25_LMS") (class "Default")
      (node (ref "R143") (pin "1") (pinfunction "1_1") (pintype "passive"))
    )
    (net (code "52") (name "VCC1P25_LMS_DIG") (class "Default")
      (node (ref "R152") (pin "1") (pinfunction "1_1") (pintype "passive"))
    )
    (net (code "53") (name "VCC2P5") (class "Default")
      (node (ref "R125") (pin "2") (pinfunction "2_2") (pintype "passive"))
      (node (ref "R126") (pin "1") (pinfunction "1_1") (pintype "passive"))
    )
    (net (code "54") (name "VCC3P3") (class "Default")
      (node (ref "C351") (pin "2") (pinfunction "2_2") (pintype "passive"))
      (node (ref "C356") (pin "2") (pinfunction "2_2") (pintype "passive"))
      (node (ref "C359") (pin "2") (pinfunction "2_2") (pintype "passive"))
      (node (ref "C360") (pin "2") (pinfunction "2_2") (pintype "passive"))
      (node (ref "C361") (pin "2") (pinfunction "2_2") (pintype "passive"))
      (node (ref "C364") (pin "2") (pinfunction "2_2") (pintype "passive"))
      (node (ref "C369") (pin "2") (pinfunction "2_2") (pintype "passive"))
      (node (ref "C376") (pin "2") (pinfunction "2_2") (pintype "passive"))
      (node (ref "C378") (pin "2") (pinfunction "2_2") (pintype "passive"))
      (node (ref "C388") (pin "2") (pinfunction "2_2") (pintype "passive"))
      (node (ref "C390") (pin "2") (pinfunction "2_2") (pintype "passive"))
      (node (ref "FR50") (pin "1") (pinfunction "1_1") (pintype "passive"))
      (node (ref "FR51") (pin "1") (pinfunction "1_1") (pintype "passive"))
      (node (ref "FR52") (pin "1") (pinfunction "1_1") (pintype "passive"))
      (node (ref "FR53") (pin "1") (pinfunction "1_1") (pintype "passive"))
      (node (ref "IC16") (pin "1") (pinfunction "EN_1") (pintype "passive"))
      (node (ref "IC16") (pin "2") (pinfunction "IN_2") (pintype "passive"))
      (node (ref "IC21") (pin "10") (pinfunction "VIN_10") (pintype "passive"))
      (node (ref "IC24") (pin "1") (pinfunction "EN_1") (pintype "passive"))
      (node (ref "IC24") (pin "2") (pinfunction "IN_2") (pintype "passive"))
      (node (ref "IC26") (pin "1") (pinfunction "EN_1") (pintype "passive"))
      (node (ref "IC26") (pin "2") (pinfunction "IN_2") (pintype "passive"))
      (node (ref "L1") (pin "2") (pinfunction "2_2") (pintype "passive"))
      (node (ref "R122") (pin "2") (pinfunction "2_2") (pintype "passive"))
      (node (ref "R129") (pin "2") (pinfunction "2_2") (pintype "passive"))
      (node (ref "R133") (pin "1") (pinfunction "1_1") (pintype "passive"))
      (node (ref "R137") (pin "1") (pinfunction "1_1") (pintype "passive"))
      (node (ref "R139") (pin "1") (pinfunction "1_1") (pintype "passive"))
    )
    (net (code "55") (name "VCC3P3_CLK") (class "Default")
      (node (ref "R158") (pin "1") (pinfunction "1_1") (pintype "passive"))
    )
    (net (code "56") (name "VCC12P0") (class "Default")
      (node (ref "C344") (pin "2") (pinfunction "2_2") (pintype "passive"))
      (node (ref "C345") (pin "2") (pinfunction "2_2") (pintype "passive"))
      (node (ref "C346") (pin "2") (pinfunction "2_2") (pintype "passive"))
      (node (ref "C347") (pin "2") (pinfunction "2_2") (pintype "passive"))
      (node (ref "C348") (pin "2") (pinfunction "2_2") (pintype "passive"))
      (node (ref "C349") (pin "1") (pinfunction "1_1") (pintype "passive"))
      (node (ref "C353") (pin "1") (pinfunction "1_1") (pintype "passive"))
      (node (ref "C355") (pin "2") (pinfunction "2_2") (pintype "passive"))
      (node (ref "C375") (pin "2") (pinfunction "2_2") (pintype "passive"))
      (node (ref "C395") (pin "2") (pinfunction "2_2") (pintype "passive"))
      (node (ref "FR54") (pin "1") (pinfunction "1_1") (pintype "passive"))
      (node (ref "IC17") (pin "1") (pinfunction "OUT_1") (pintype "passive"))
      (node (ref "IC17") (pin "6") (pinfunction "VDD_6") (pintype "passive"))
      (node (ref "IC18") (pin "1") (pinfunction "OUT_1") (pintype "passive"))
      (node (ref "IC18") (pin "6") (pinfunction "VDD_6") (pintype "passive"))
      (node (ref "IC20") (pin "16") (pinfunction "PVIN_16") (pintype "passive"))
      (node (ref "IC20") (pin "17") (pinfunction "PVIN_17") (pintype "passive"))
      (node (ref "IC20") (pin "18") (pinfunction "PVIN_18") (pintype "passive"))
      (node (ref "IC20") (pin "19") (pinfunction "PVIN_19") (pintype "passive"))
      (node (ref "IC20") (pin "20") (pinfunction "EN_20") (pintype "passive"))
      (node (ref "IC23") (pin "16") (pinfunction "PVIN_16") (pintype "passive"))
      (node (ref "IC23") (pin "17") (pinfunction "PVIN_17") (pintype "passive"))
      (node (ref "IC23") (pin "18") (pinfunction "PVIN_18") (pintype "passive"))
      (node (ref "IC23") (pin "19") (pinfunction "PVIN_19") (pintype "passive"))
      (node (ref "IC23") (pin "20") (pinfunction "EN_20") (pintype "passive"))
      (node (ref "J17") (pin "2") (pinfunction "2_2") (pintype "passive"))
      (node (ref "R123") (pin "1") (pinfunction "1_1") (pintype "passive"))
      (node (ref "R124") (pin "1") (pinfunction "1_1") (pintype "passive"))
      (node (ref "VT2") (pin "5") (pinfunction "D_5") (pintype "passive"))
      (node (ref "VT2") (pin "6") (pinfunction "D_6") (pintype "passive"))
      (node (ref "VT2") (pin "7") (pinfunction "D_7") (pintype "passive"))
      (node (ref "VT2") (pin "8") (pinfunction "D_8") (pintype "passive"))
      (node (ref "VT3") (pin "5") (pinfunction "D_5") (pintype "passive"))
      (node (ref "VT3") (pin "6") (pinfunction "D_6") (pintype "passive"))
      (node (ref "VT3") (pin "7") (pinfunction "D_7") (pintype "passive"))
      (node (ref "VT3") (pin "8") (pinfunction "D_8") (pintype "passive"))
    )
    (net (code "57") (name "VCC12P0_PCIE") (class "Default")
      (node (ref "IC17") (pin "2") (pinfunction "IN_2") (pintype "passive"))
      (node (ref "R124") (pin "2") (pinfunction "2_2") (pintype "passive"))
      (node (ref "VT3") (pin "1") (pinfunction "S_1") (pintype "passive"))
      (node (ref "VT3") (pin "2") (pinfunction "S_2") (pintype "passive"))
      (node (ref "VT3") (pin "3") (pinfunction "S_3") (pintype "passive"))
    )
    (net (code "58") (name "VDIO_LMS") (class "Default")
      (node (ref "C342") (pin "2") (pinfunction "2_2") (pintype "passive"))
      (node (ref "C343") (pin "1") (pinfunction "1_1") (pintype "passive"))
      (node (ref "FR49") (pin "2") (pinfunction "2_2") (pintype "passive"))
    )
    (net (code "59") (name "VDIO_LMS_FPGA") (class "Default")
      (node (ref "FR49") (pin "1") (pinfunction "1_1") (pintype "passive"))
      (node (ref "R122") (pin "1") (pinfunction "1_1") (pintype "passive"))
      (node (ref "R125") (pin "1") (pinfunction "1_1") (pintype "passive"))
    )
    (net (code "60") (name "VREF_DDR2") (class "Default")
      (node (ref "C373") (pin "1") (pinfunction "1_1") (pintype "passive"))
      (node (ref "IC21") (pin "6") (pinfunction "VTTREF_6") (pintype "passive"))
    )
    (net (code "61") (name "VTT_DDR2") (class "Default")
      (node (ref "C371") (pin "2") (pinfunction "2_2") (pintype "passive"))
      (node (ref "C372") (pin "2") (pinfunction "2_2") (pintype "passive"))
      (node (ref "IC21") (pin "3") (pinfunction "VTT_3") (pintype "passive"))
      (node (ref "IC21") (pin "5") (pinfunction "VTTSNS_5") (pintype "passive"))
    )
    (net (code "62") (name "unconnected-(IC17-NC-Pad5)") (class "Default")
      (node (ref "IC17") (pin "5") (pinfunction "NC_5") (pintype "passive+no_connect"))
    )
    (net (code "63") (name "unconnected-(IC18-NC-Pad5)") (class "Default")
      (node (ref "IC18") (pin "5") (pinfunction "NC_5") (pintype "passive+no_connect"))
    )
    (net (code "64") (name "unconnected-(IC20-PGOOD-Pad21)") (class "Default")
      (node (ref "IC20") (pin "21") (pinfunction "PGOOD_21") (pintype "passive+no_connect"))
    )
    (net (code "65") (name "unconnected-(IC20-SYNC-Pad23)") (class "Default")
      (node (ref "IC20") (pin "23") (pinfunction "SYNC_23") (pintype "passive+no_connect"))
    )
    (net (code "66") (name "unconnected-(IC23-PGOOD-Pad21)") (class "Default")
      (node (ref "IC23") (pin "21") (pinfunction "PGOOD_21") (pintype "passive+no_connect"))
    )
    (net (code "67") (name "unconnected-(IC23-SYNC-Pad23)") (class "Default")
      (node (ref "IC23") (pin "23") (pinfunction "SYNC_23") (pintype "passive+no_connect"))
    )
    (net (code "68") (name "unconnected-(IC27-NC-Pad1)") (class "Default")
      (node (ref "IC27") (pin "1") (pinfunction "NC_1") (pintype "passive+no_connect"))
    )
  )
)
